# mcu_adapter.net
KiCad netlist of a schematic drawn in EAGLE
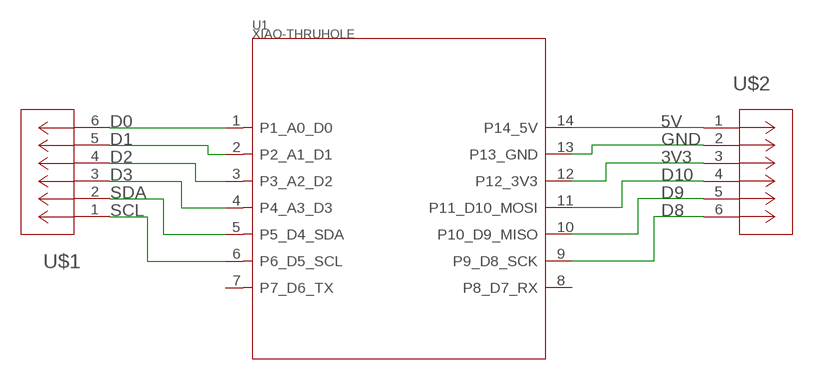
[diagram p0: schematic, sheet 1]

(export (version "E")
  (design (tool "Eeschema 10.0.6"))
  (components
    (comp (ref "U$1")
      (value "NRPN032PAEN-RC")
      (footprint "eagle-import:CONN3X2_NRPN032PAEN-RC")
      (libsource (lib "eagle-import") (part "NRPN032PAEN-RC"))
    )
    (comp (ref "U$2")
      (value "NRPN032PAEN-RC")
      (footprint "eagle-import:CONN3X2_NRPN032PAEN-RC")
      (libsource (lib "eagle-import") (part "NRPN032PAEN-RC"))
    )
    (comp (ref "U1")
      (value "XIAO-THRUHOLE")
      (footprint "eagle-import:XIAO-GENERIC-THRUHOLE-MODULE14P-2.54-21X17.8MM")
      (libsource (lib "eagle-import") (part "XIAO-THRUHOLE"))
    )
  )
  (nets
    (net (code "1") (name "/3V3") (class "Default")
      (node (ref "U$2") (pin "3") (pinfunction "3_3") (pintype "passive"))
      (node (ref "U1") (pin "12") (pinfunction "P12_3V3_12") (pintype "bidirectional"))
    )
    (net (code "2") (name "/5V") (class "Default")
      (node (ref "U$2") (pin "1") (pinfunction "1_1") (pintype "passive"))
      (node (ref "U1") (pin "14") (pinfunction "P14_5V_14") (pintype "bidirectional"))
    )
    (net (code "3") (name "/D0") (class "Default")
      (node (ref "U$1") (pin "6") (pinfunction "6_6") (pintype "passive"))
      (node (ref "U1") (pin "1") (pinfunction "P1_A0_D0_1") (pintype "bidirectional"))
    )
    (net (code "4") (name "/D1") (class "Default")
      (node (ref "U$1") (pin "5") (pinfunction "5_5") (pintype "passive"))
      (node (ref "U1") (pin "2") (pinfunction "P2_A1_D1_2") (pintype "bidirectional"))
    )
    (net (code "5") (name "/D2") (class "Default")
      (node (ref "U$1") (pin "4") (pinfunction "4_4") (pintype "passive"))
      (node (ref "U1") (pin "3") (pinfunction "P3_A2_D2_3") (pintype "bidirectional"))
    )
    (net (code "6") (name "/D3") (class "Default")
      (node (ref "U$1") (pin "3") (pinfunction "3_3") (pintype "passive"))
      (node (ref "U1") (pin "4") (pinfunction "P4_A3_D3_4") (pintype "bidirectional"))
    )
    (net (code "7") (name "/D8") (class "Default")
      (node (ref "U$2") (pin "6") (pinfunction "6_6") (pintype "passive"))
      (node (ref "U1") (pin "9") (pinfunction "P9_D8_SCK_9") (pintype "bidirectional"))
    )
    (net (code "8") (name "/D9") (class "Default")
      (node (ref "U$2") (pin "5") (pinfunction "5_5") (pintype "passive"))
      (node (ref "U1") (pin "10") (pinfunction "P10_D9_MISO_10") (pintype "bidirectional"))
    )
    (net (code "9") (name "/D10") (class "Default")
      (node (ref "U$2") (pin "4") (pinfunction "4_4") (pintype "passive"))
      (node (ref "U1") (pin "11") (pinfunction "P11_D10_MOSI_11") (pintype "bidirectional"))
    )
    (net (code "10") (name "/GND") (class "Default")
      (node (ref "U$2") (pin "2") (pinfunction "2_2") (pintype "passive"))
      (node (ref "U1") (pin "13") (pinfunction "P13_GND_13") (pintype "bidirectional"))
    )
    (net (code "11") (name "/SCL") (class "Default")
      (node (ref "U$1") (pin "1") (pinfunction "1_1") (pintype "passive"))
      (node (ref "U1") (pin "6") (pinfunction "P6_D5_SCL_6") (pintype "bidirectional"))
    )
    (net (code "12") (name "/SDA") (class "Default")
      (node (ref "U$1") (pin "2") (pinfunction "2_2") (pintype "passive"))
      (node (ref "U1") (pin "5") (pinfunction "P5_D4_SDA_5") (pintype "bidirectional"))
    )
    (net (code "13") (name "unconnected-(U1-P7_D6_TX-Pad7)") (class "Default")
      (node (ref "U1") (pin "7") (pinfunction "P7_D6_TX_7") (pintype "bidirectional"))
    )
    (net (code "14") (name "unconnected-(U1-P8_D7_RX-Pad8)") (class "Default")
      (node (ref "U1") (pin "8") (pinfunction "P8_D7_RX_8") (pintype "bidirectional"))
    )
  )
)
